# Shield_Release_181017.net
KiCad netlist of a schematic drawn in EAGLE
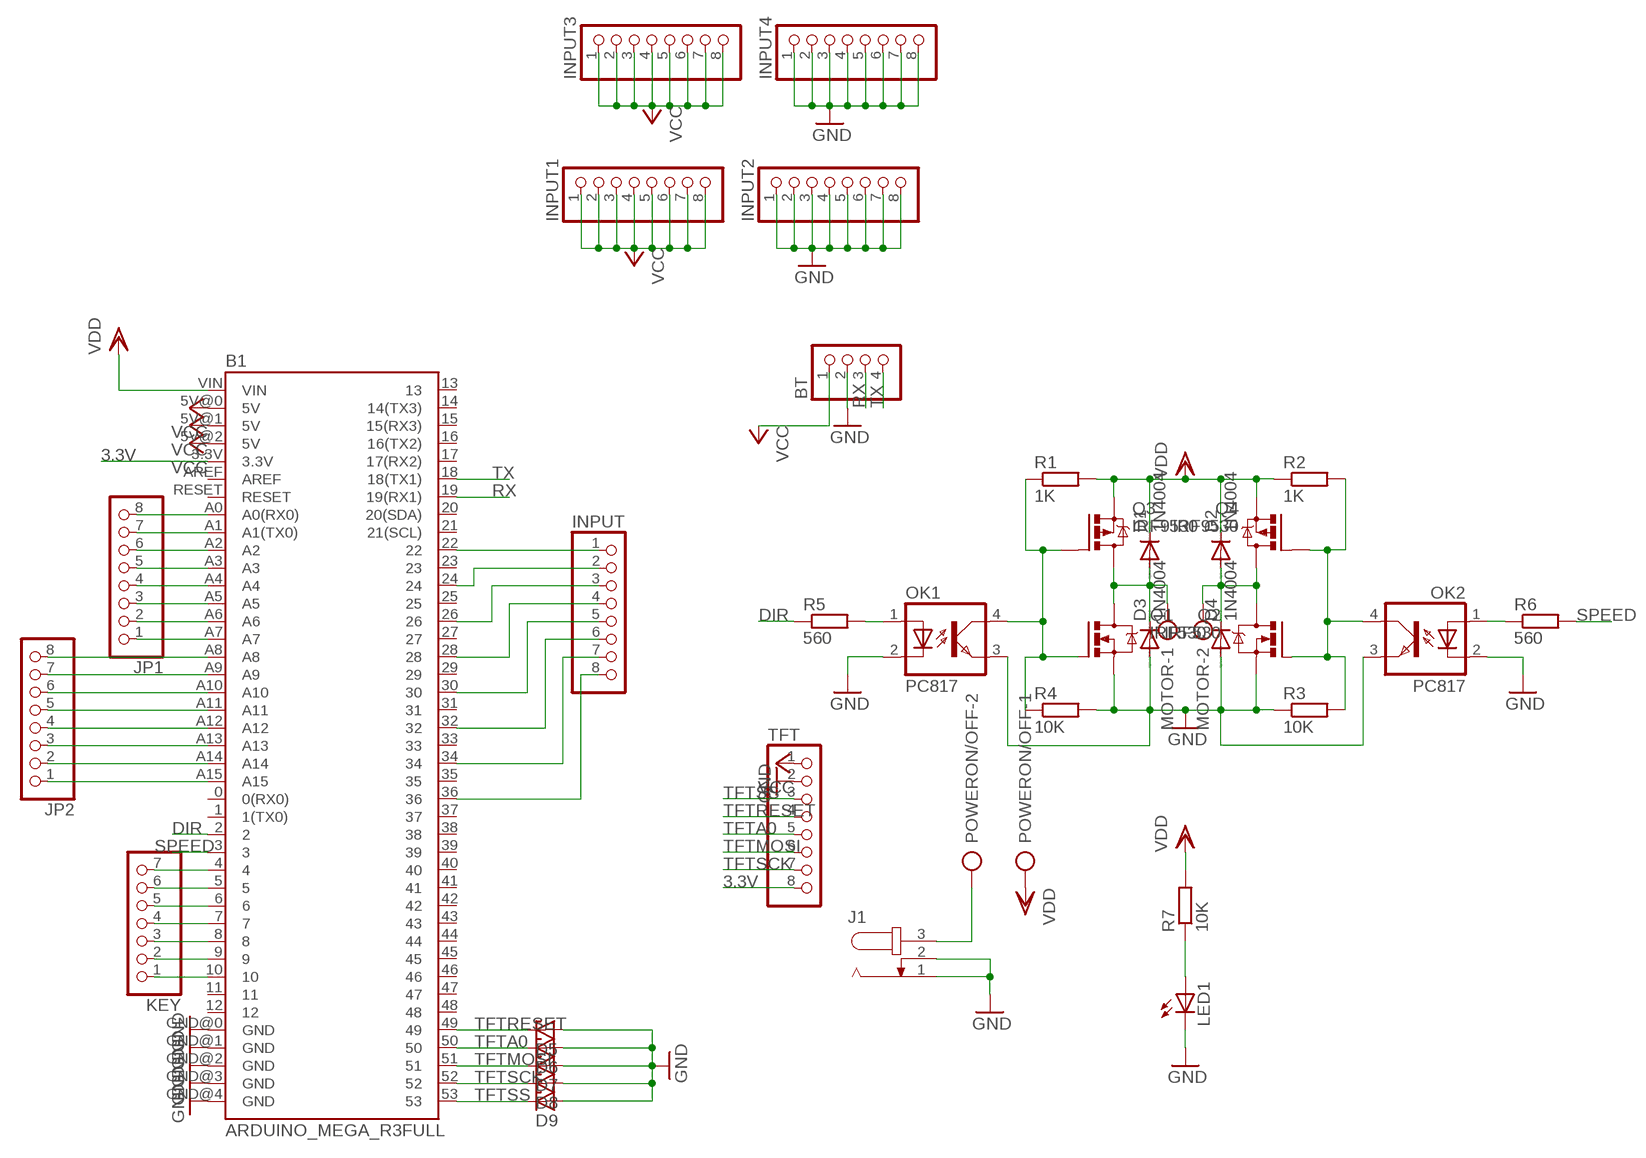
[diagram p0: schematic, sheet 1]

(export (version "E")
  (design (tool "Eeschema 10.0.6"))
  (components
    (comp (ref "B1")
      (value "ARDUINO_MEGA_R3FULL")
      (footprint "eagle-import:ARDUINO_MEGA")
      (libsource (lib "eagle-import") (part "ARDUINO_MEGA_R3FULL"))
    )
    (comp (ref "BT")
      (value "PINHD-1X4")
      (footprint "eagle-import:1X04")
      (libsource (lib "eagle-import") (part "PINHD-1X4"))
    )
    (comp (ref "D1")
      (value "1N4004")
      (footprint "eagle-import:DO41-10")
      (libsource (lib "eagle-import") (part "1N4004"))
    )
    (comp (ref "D2")
      (value "1N4004")
      (footprint "eagle-import:DO41-10")
      (libsource (lib "eagle-import") (part "1N4004"))
    )
    (comp (ref "D3")
      (value "1N4004")
      (footprint "eagle-import:DO41-10")
      (libsource (lib "eagle-import") (part "1N4004"))
    )
    (comp (ref "D4")
      (value "1N4004")
      (footprint "eagle-import:DO41-10")
      (libsource (lib "eagle-import") (part "1N4004"))
    )
    (comp (ref "D5")
      (value "ZENER-DIODEDO41Z10")
      (footprint "eagle-import:DO41Z10")
      (libsource (lib "eagle-import") (part "ZENER-DIODEDO41Z10"))
    )
    (comp (ref "D6")
      (value "ZENER-DIODEDO41Z10")
      (footprint "eagle-import:DO41Z10")
      (libsource (lib "eagle-import") (part "ZENER-DIODEDO41Z10"))
    )
    (comp (ref "D7")
      (value "ZENER-DIODEDO41Z10")
      (footprint "eagle-import:DO41Z10")
      (libsource (lib "eagle-import") (part "ZENER-DIODEDO41Z10"))
    )
    (comp (ref "D8")
      (value "ZENER-DIODEDO41Z10")
      (footprint "eagle-import:DO41Z10")
      (libsource (lib "eagle-import") (part "ZENER-DIODEDO41Z10"))
    )
    (comp (ref "D9")
      (value "ZENER-DIODEDO41Z10")
      (footprint "eagle-import:DO41Z10")
      (libsource (lib "eagle-import") (part "ZENER-DIODEDO41Z10"))
    )
    (comp (ref "INPUT")
      (value "PINHD-1X8")
      (footprint "eagle-import:1X08")
      (libsource (lib "eagle-import") (part "PINHD-1X8"))
    )
    (comp (ref "INPUT1")
      (value "PINHD-1X8")
      (footprint "eagle-import:1X08")
      (libsource (lib "eagle-import") (part "PINHD-1X8"))
    )
    (comp (ref "INPUT2")
      (value "PINHD-1X8")
      (footprint "eagle-import:1X08")
      (libsource (lib "eagle-import") (part "PINHD-1X8"))
    )
    (comp (ref "INPUT3")
      (value "PINHD-1X8")
      (footprint "eagle-import:1X08")
      (libsource (lib "eagle-import") (part "PINHD-1X8"))
    )
    (comp (ref "INPUT4")
      (value "PINHD-1X8")
      (footprint "eagle-import:1X08")
      (libsource (lib "eagle-import") (part "PINHD-1X8"))
    )
    (comp (ref "J1")
      (value "JACK-PLUG0")
      (footprint "eagle-import:SPC4077")
      (libsource (lib "eagle-import") (part "JACK-PLUG0"))
    )
    (comp (ref "JP1")
      (value "PINHD-1X8")
      (footprint "eagle-import:1X08")
      (libsource (lib "eagle-import") (part "PINHD-1X8"))
    )
    (comp (ref "JP2")
      (value "PINHD-1X8")
      (footprint "eagle-import:1X08")
      (libsource (lib "eagle-import") (part "PINHD-1X8"))
    )
    (comp (ref "KEY")
      (value "PINHD-1X7")
      (footprint "eagle-import:1X07")
      (libsource (lib "eagle-import") (part "PINHD-1X7"))
    )
    (comp (ref "LED1")
      (value "LED5MM")
      (footprint "eagle-import:LED5MM")
      (libsource (lib "eagle-import") (part "LED5MM"))
    )
    (comp (ref "MOTOR")
      (value "AK300/2")
      (footprint "eagle-import:AK300_2")
      (libsource (lib "eagle-import") (part "AK300/2"))
    )
    (comp (ref "OK1")
      (value "PC817")
      (footprint "eagle-import:DIL04")
      (fields (field (name "MPN") "PC817X4J000F"))
      (libsource (lib "eagle-import") (part "PC817"))
    )
    (comp (ref "OK2")
      (value "PC817")
      (footprint "eagle-import:DIL04")
      (fields (field (name "MPN") "PC817X4J000F"))
      (libsource (lib "eagle-import") (part "PC817"))
    )
    (comp (ref "POWERON/OFF")
      (value "AK300/2")
      (footprint "eagle-import:AK300_2")
      (libsource (lib "eagle-import") (part "AK300/2"))
    )
    (comp (ref "Q1")
      (value "IRF530")
      (footprint "eagle-import:TO220BV")
      (libsource (lib "eagle-import") (part "IRF530"))
    )
    (comp (ref "Q2")
      (value "IRF530")
      (footprint "eagle-import:TO220BV")
      (libsource (lib "eagle-import") (part "IRF530"))
    )
    (comp (ref "Q3")
      (value "IRF9530")
      (footprint "eagle-import:TO220BV")
      (libsource (lib "eagle-import") (part "IRF9530"))
    )
    (comp (ref "Q4")
      (value "IRF9530")
      (footprint "eagle-import:TO220BV")
      (libsource (lib "eagle-import") (part "IRF9530"))
    )
    (comp (ref "R1")
      (value "1K")
      (footprint "eagle-import:0204_7")
      (libsource (lib "eagle-import") (part "R-EU_0204/7"))
    )
    (comp (ref "R2")
      (value "1K")
      (footprint "eagle-import:0204_7")
      (libsource (lib "eagle-import") (part "R-EU_0204/7"))
    )
    (comp (ref "R3")
      (value "10K")
      (footprint "eagle-import:0204_7")
      (libsource (lib "eagle-import") (part "R-EU_0204/7"))
    )
    (comp (ref "R4")
      (value "10K")
      (footprint "eagle-import:0204_7")
      (libsource (lib "eagle-import") (part "R-EU_0204/7"))
    )
    (comp (ref "R5")
      (value "560")
      (footprint "eagle-import:0204_7")
      (libsource (lib "eagle-import") (part "R-EU_0204/7"))
    )
    (comp (ref "R6")
      (value "560")
      (footprint "eagle-import:0204_7")
      (libsource (lib "eagle-import") (part "R-EU_0204/7"))
    )
    (comp (ref "R7")
      (value "10K")
      (footprint "eagle-import:0204_7")
      (libsource (lib "eagle-import") (part "R-EU_0204/7"))
    )
    (comp (ref "TFT")
      (value "PINHD-1X8")
      (footprint "eagle-import:1X08")
      (libsource (lib "eagle-import") (part "PINHD-1X8"))
    )
  )
  (nets
    (net (code "1") (name "/3.3V") (class "Default")
      (node (ref "B1") (pin "3.3V") (pinfunction "3.3V_3.3V") (pintype "bidirectional"))
      (node (ref "TFT") (pin "8") (pinfunction "8_8") (pintype "passive"))
    )
    (net (code "2") (name "/DIR") (class "Default")
      (node (ref "B1") (pin "2") (pinfunction "2_2") (pintype "bidirectional"))
      (node (ref "R5") (pin "1") (pinfunction "1_1") (pintype "passive"))
    )
    (net (code "3") (name "/RX") (class "Default")
      (node (ref "B1") (pin "19") (pinfunction "19(RX1)_19") (pintype "bidirectional"))
      (node (ref "BT") (pin "3") (pinfunction "3_3") (pintype "passive"))
    )
    (net (code "4") (name "/SPEED") (class "Default")
      (node (ref "B1") (pin "3") (pinfunction "3_3") (pintype "bidirectional"))
      (node (ref "R6") (pin "2") (pinfunction "2_2") (pintype "passive"))
    )
    (net (code "5") (name "/TFTA0") (class "Default")
      (node (ref "B1") (pin "50") (pinfunction "50_50") (pintype "bidirectional"))
      (node (ref "D6") (pin "C") (pinfunction "C_C") (pintype "passive"))
      (node (ref "TFT") (pin "5") (pinfunction "5_5") (pintype "passive"))
    )
    (net (code "6") (name "/TFTMOSI") (class "Default")
      (node (ref "B1") (pin "51") (pinfunction "51_51") (pintype "bidirectional"))
      (node (ref "D7") (pin "C") (pinfunction "C_C") (pintype "passive"))
      (node (ref "TFT") (pin "6") (pinfunction "6_6") (pintype "passive"))
    )
    (net (code "7") (name "/TFTRESET") (class "Default")
      (node (ref "B1") (pin "49") (pinfunction "49_49") (pintype "bidirectional"))
      (node (ref "D5") (pin "C") (pinfunction "C_C") (pintype "passive"))
      (node (ref "TFT") (pin "4") (pinfunction "4_4") (pintype "passive"))
    )
    (net (code "8") (name "/TFTSCK") (class "Default")
      (node (ref "B1") (pin "52") (pinfunction "52_52") (pintype "bidirectional"))
      (node (ref "D8") (pin "C") (pinfunction "C_C") (pintype "passive"))
      (node (ref "TFT") (pin "7") (pinfunction "7_7") (pintype "passive"))
    )
    (net (code "9") (name "/TFTSS") (class "Default")
      (node (ref "B1") (pin "53") (pinfunction "53_53") (pintype "bidirectional"))
      (node (ref "D9") (pin "C") (pinfunction "C_C") (pintype "passive"))
      (node (ref "TFT") (pin "3") (pinfunction "3_3") (pintype "passive"))
    )
    (net (code "10") (name "/TX") (class "Default")
      (node (ref "B1") (pin "18") (pinfunction "18(TX1)_18") (pintype "bidirectional"))
      (node (ref "BT") (pin "4") (pinfunction "4_4") (pintype "passive"))
    )
    (net (code "11") (name "GND") (class "Default")
      (node (ref "B1") (pin "GND@0") (pinfunction "GND_GND@0") (pintype "bidirectional"))
      (node (ref "B1") (pin "GND@1") (pinfunction "GND_GND@1") (pintype "bidirectional"))
      (node (ref "B1") (pin "GND@2") (pinfunction "GND_GND@2") (pintype "bidirectional"))
      (node (ref "B1") (pin "GND@3") (pinfunction "GND_GND@3") (pintype "bidirectional"))
      (node (ref "B1") (pin "GND@4") (pinfunction "GND_GND@4") (pintype "bidirectional"))
      (node (ref "BT") (pin "2") (pinfunction "2_2") (pintype "passive"))
      (node (ref "D3") (pin "A") (pinfunction "A_A") (pintype "passive"))
      (node (ref "D4") (pin "A") (pinfunction "A_A") (pintype "passive"))
      (node (ref "D5") (pin "A") (pinfunction "A_A") (pintype "passive"))
      (node (ref "D6") (pin "A") (pinfunction "A_A") (pintype "passive"))
      (node (ref "D7") (pin "A") (pinfunction "A_A") (pintype "passive"))
      (node (ref "D8") (pin "A") (pinfunction "A_A") (pintype "passive"))
      (node (ref "D9") (pin "A") (pinfunction "A_A") (pintype "passive"))
      (node (ref "INPUT2") (pin "1") (pinfunction "1_1") (pintype "passive"))
      (node (ref "INPUT2") (pin "2") (pinfunction "2_2") (pintype "passive"))
      (node (ref "INPUT2") (pin "3") (pinfunction "3_3") (pintype "passive"))
      (node (ref "INPUT2") (pin "4") (pinfunction "4_4") (pintype "passive"))
      (node (ref "INPUT2") (pin "5") (pinfunction "5_5") (pintype "passive"))
      (node (ref "INPUT2") (pin "6") (pinfunction "6_6") (pintype "passive"))
      (node (ref "INPUT2") (pin "7") (pinfunction "7_7") (pintype "passive"))
      (node (ref "INPUT2") (pin "8") (pinfunction "8_8") (pintype "passive"))
      (node (ref "INPUT4") (pin "1") (pinfunction "1_1") (pintype "passive"))
      (node (ref "INPUT4") (pin "2") (pinfunction "2_2") (pintype "passive"))
      (node (ref "INPUT4") (pin "3") (pinfunction "3_3") (pintype "passive"))
      (node (ref "INPUT4") (pin "4") (pinfunction "4_4") (pintype "passive"))
      (node (ref "INPUT4") (pin "5") (pinfunction "5_5") (pintype "passive"))
      (node (ref "INPUT4") (pin "6") (pinfunction "6_6") (pintype "passive"))
      (node (ref "INPUT4") (pin "7") (pinfunction "7_7") (pintype "passive"))
      (node (ref "INPUT4") (pin "8") (pinfunction "8_8") (pintype "passive"))
      (node (ref "J1") (pin "1") (pinfunction "1_1") (pintype "passive"))
      (node (ref "J1") (pin "2") (pinfunction "2_2") (pintype "passive"))
      (node (ref "LED1") (pin "K") (pinfunction "C_K") (pintype "passive"))
      (node (ref "OK1") (pin "2") (pinfunction "C_2") (pintype "passive"))
      (node (ref "OK1") (pin "3") (pinfunction "EMIT_3") (pintype "passive"))
      (node (ref "OK2") (pin "2") (pinfunction "C_2") (pintype "passive"))
      (node (ref "OK2") (pin "3") (pinfunction "EMIT_3") (pintype "passive"))
      (node (ref "Q1") (pin "S") (pinfunction "S_S") (pintype "passive"))
      (node (ref "Q2") (pin "S") (pinfunction "S_S") (pintype "passive"))
      (node (ref "R3") (pin "1") (pinfunction "1_1") (pintype "passive"))
      (node (ref "R4") (pin "2") (pinfunction "2_2") (pintype "passive"))
      (node (ref "TFT") (pin "2") (pinfunction "2_2") (pintype "passive"))
    )
    (net (code "12") (name "Net-(B1-A0(RX0))") (class "Default")
      (node (ref "B1") (pin "A0") (pinfunction "A0(RX0)_A0") (pintype "bidirectional"))
      (node (ref "JP1") (pin "8") (pinfunction "8_8") (pintype "passive"))
    )
    (net (code "13") (name "Net-(B1-A1(TX0))") (class "Default")
      (node (ref "B1") (pin "A1") (pinfunction "A1(TX0)_A1") (pintype "bidirectional"))
      (node (ref "JP1") (pin "7") (pinfunction "7_7") (pintype "passive"))
    )
    (net (code "14") (name "Net-(B1-Pad4)") (class "Default")
      (node (ref "B1") (pin "4") (pinfunction "4_4") (pintype "bidirectional"))
      (node (ref "KEY") (pin "7") (pinfunction "7_7") (pintype "passive"))
    )
    (net (code "15") (name "Net-(B1-Pad5)") (class "Default")
      (node (ref "B1") (pin "5") (pinfunction "5_5") (pintype "bidirectional"))
      (node (ref "KEY") (pin "6") (pinfunction "6_6") (pintype "passive"))
    )
    (net (code "16") (name "Net-(B1-Pad6)") (class "Default")
      (node (ref "B1") (pin "6") (pinfunction "6_6") (pintype "bidirectional"))
      (node (ref "KEY") (pin "5") (pinfunction "5_5") (pintype "passive"))
    )
    (net (code "17") (name "Net-(B1-Pad7)") (class "Default")
      (node (ref "B1") (pin "7") (pinfunction "7_7") (pintype "bidirectional"))
      (node (ref "KEY") (pin "4") (pinfunction "4_4") (pintype "passive"))
    )
    (net (code "18") (name "Net-(B1-Pad8)") (class "Default")
      (node (ref "B1") (pin "8") (pinfunction "8_8") (pintype "bidirectional"))
      (node (ref "KEY") (pin "3") (pinfunction "3_3") (pintype "passive"))
    )
    (net (code "19") (name "Net-(B1-Pad9)") (class "Default")
      (node (ref "B1") (pin "9") (pinfunction "9_9") (pintype "bidirectional"))
      (node (ref "KEY") (pin "2") (pinfunction "2_2") (pintype "passive"))
    )
    (net (code "20") (name "Net-(B1-Pad10)") (class "Default")
      (node (ref "B1") (pin "10") (pinfunction "10_10") (pintype "bidirectional"))
      (node (ref "KEY") (pin "1") (pinfunction "1_1") (pintype "passive"))
    )
    (net (code "21") (name "Net-(B1-Pad22)") (class "Default")
      (node (ref "B1") (pin "22") (pinfunction "22_22") (pintype "bidirectional"))
      (node (ref "INPUT") (pin "1") (pinfunction "1_1") (pintype "passive"))
    )
    (net (code "22") (name "Net-(B1-Pad24)") (class "Default")
      (node (ref "B1") (pin "24") (pinfunction "24_24") (pintype "bidirectional"))
      (node (ref "INPUT") (pin "2") (pinfunction "2_2") (pintype "passive"))
    )
    (net (code "23") (name "Net-(B1-Pad26)") (class "Default")
      (node (ref "B1") (pin "26") (pinfunction "26_26") (pintype "bidirectional"))
      (node (ref "INPUT") (pin "3") (pinfunction "3_3") (pintype "passive"))
    )
    (net (code "24") (name "Net-(B1-Pad28)") (class "Default")
      (node (ref "B1") (pin "28") (pinfunction "28_28") (pintype "bidirectional"))
      (node (ref "INPUT") (pin "4") (pinfunction "4_4") (pintype "passive"))
    )
    (net (code "25") (name "Net-(B1-Pad30)") (class "Default")
      (node (ref "B1") (pin "30") (pinfunction "30_30") (pintype "bidirectional"))
      (node (ref "INPUT") (pin "5") (pinfunction "5_5") (pintype "passive"))
    )
    (net (code "26") (name "Net-(B1-Pad32)") (class "Default")
      (node (ref "B1") (pin "32") (pinfunction "32_32") (pintype "bidirectional"))
      (node (ref "INPUT") (pin "6") (pinfunction "6_6") (pintype "passive"))
    )
    (net (code "27") (name "Net-(B1-Pad34)") (class "Default")
      (node (ref "B1") (pin "34") (pinfunction "34_34") (pintype "bidirectional"))
      (node (ref "INPUT") (pin "7") (pinfunction "7_7") (pintype "passive"))
    )
    (net (code "28") (name "Net-(B1-Pad36)") (class "Default")
      (node (ref "B1") (pin "36") (pinfunction "36_36") (pintype "bidirectional"))
      (node (ref "INPUT") (pin "8") (pinfunction "8_8") (pintype "passive"))
    )
    (net (code "29") (name "Net-(B1-PadA2)") (class "Default")
      (node (ref "B1") (pin "A2") (pinfunction "A2_A2") (pintype "bidirectional"))
      (node (ref "JP1") (pin "6") (pinfunction "6_6") (pintype "passive"))
    )
    (net (code "30") (name "Net-(B1-PadA3)") (class "Default")
      (node (ref "B1") (pin "A3") (pinfunction "A3_A3") (pintype "bidirectional"))
      (node (ref "JP1") (pin "5") (pinfunction "5_5") (pintype "passive"))
    )
    (net (code "31") (name "Net-(B1-PadA4)") (class "Default")
      (node (ref "B1") (pin "A4") (pinfunction "A4_A4") (pintype "bidirectional"))
      (node (ref "JP1") (pin "4") (pinfunction "4_4") (pintype "passive"))
    )
    (net (code "32") (name "Net-(B1-PadA5)") (class "Default")
      (node (ref "B1") (pin "A5") (pinfunction "A5_A5") (pintype "bidirectional"))
      (node (ref "JP1") (pin "3") (pinfunction "3_3") (pintype "passive"))
    )
    (net (code "33") (name "Net-(B1-PadA6)") (class "Default")
      (node (ref "B1") (pin "A6") (pinfunction "A6_A6") (pintype "bidirectional"))
      (node (ref "JP1") (pin "2") (pinfunction "2_2") (pintype "passive"))
    )
    (net (code "34") (name "Net-(B1-PadA7)") (class "Default")
      (node (ref "B1") (pin "A7") (pinfunction "A7_A7") (pintype "bidirectional"))
      (node (ref "JP1") (pin "1") (pinfunction "1_1") (pintype "passive"))
    )
    (net (code "35") (name "Net-(B1-PadA8)") (class "Default")
      (node (ref "B1") (pin "A8") (pinfunction "A8_A8") (pintype "bidirectional"))
      (node (ref "JP2") (pin "8") (pinfunction "8_8") (pintype "passive"))
    )
    (net (code "36") (name "Net-(B1-PadA9)") (class "Default")
      (node (ref "B1") (pin "A9") (pinfunction "A9_A9") (pintype "bidirectional"))
      (node (ref "JP2") (pin "7") (pinfunction "7_7") (pintype "passive"))
    )
    (net (code "37") (name "Net-(B1-PadA10)") (class "Default")
      (node (ref "B1") (pin "A10") (pinfunction "A10_A10") (pintype "bidirectional"))
      (node (ref "JP2") (pin "6") (pinfunction "6_6") (pintype "passive"))
    )
    (net (code "38") (name "Net-(B1-PadA11)") (class "Default")
      (node (ref "B1") (pin "A11") (pinfunction "A11_A11") (pintype "bidirectional"))
      (node (ref "JP2") (pin "5") (pinfunction "5_5") (pintype "passive"))
    )
    (net (code "39") (name "Net-(B1-PadA12)") (class "Default")
      (node (ref "B1") (pin "A12") (pinfunction "A12_A12") (pintype "bidirectional"))
      (node (ref "JP2") (pin "4") (pinfunction "4_4") (pintype "passive"))
    )
    (net (code "40") (name "Net-(B1-PadA13)") (class "Default")
      (node (ref "B1") (pin "A13") (pinfunction "A13_A13") (pintype "bidirectional"))
      (node (ref "JP2") (pin "3") (pinfunction "3_3") (pintype "passive"))
    )
    (net (code "41") (name "Net-(B1-PadA14)") (class "Default")
      (node (ref "B1") (pin "A14") (pinfunction "A14_A14") (pintype "bidirectional"))
      (node (ref "JP2") (pin "2") (pinfunction "2_2") (pintype "passive"))
    )
    (net (code "42") (name "Net-(B1-PadA15)") (class "Default")
      (node (ref "B1") (pin "A15") (pinfunction "A15_A15") (pintype "bidirectional"))
      (node (ref "JP2") (pin "1") (pinfunction "1_1") (pintype "passive"))
    )
    (net (code "43") (name "Net-(LED1-PadA)") (class "Default")
      (node (ref "LED1") (pin "A") (pinfunction "A_A") (pintype "passive"))
      (node (ref "R7") (pin "1") (pinfunction "1_1") (pintype "passive"))
    )
    (net (code "44") (name "Net-(MOTORA-KL)") (class "Default")
      (node (ref "D1") (pin "A") (pinfunction "A_A") (pintype "passive"))
      (node (ref "D3") (pin "C") (pinfunction "C_C") (pintype "passive"))
      (node (ref "MOTOR") (pin "1") (pinfunction "KL_1") (pintype "passive"))
      (node (ref "Q1") (pin "D") (pinfunction "D_D") (pintype "passive"))
      (node (ref "Q3") (pin "D") (pinfunction "D_D") (pintype "passive"))
    )
    (net (code "45") (name "Net-(MOTORB-KL)") (class "Default")
      (node (ref "D2") (pin "A") (pinfunction "A_A") (pintype "passive"))
      (node (ref "D4") (pin "C") (pinfunction "C_C") (pintype "passive"))
      (node (ref "MOTOR") (pin "2") (pinfunction "KL_2") (pintype "passive"))
      (node (ref "Q2") (pin "D") (pinfunction "D_D") (pintype "passive"))
      (node (ref "Q4") (pin "D") (pinfunction "D_D") (pintype "passive"))
    )
    (net (code "46") (name "Net-(OK1-A)") (class "Default")
      (node (ref "OK1") (pin "1") (pinfunction "A_1") (pintype "passive"))
      (node (ref "R5") (pin "2") (pinfunction "2_2") (pintype "passive"))
    )
    (net (code "47") (name "Net-(OK1-COL)") (class "Default")
      (node (ref "OK1") (pin "4") (pinfunction "COL_4") (pintype "passive"))
      (node (ref "Q1") (pin "G") (pinfunction "G_G") (pintype "passive"))
      (node (ref "Q3") (pin "G") (pinfunction "G_G") (pintype "passive"))
      (node (ref "R1") (pin "1") (pinfunction "1_1") (pintype "passive"))
      (node (ref "R4") (pin "1") (pinfunction "1_1") (pintype "passive"))
    )
    (net (code "48") (name "Net-(OK2-A)") (class "Default")
      (node (ref "OK2") (pin "1") (pinfunction "A_1") (pintype "passive"))
      (node (ref "R6") (pin "1") (pinfunction "1_1") (pintype "passive"))
    )
    (net (code "49") (name "Net-(OK2-COL)") (class "Default")
      (node (ref "OK2") (pin "4") (pinfunction "COL_4") (pintype "passive"))
      (node (ref "Q2") (pin "G") (pinfunction "G_G") (pintype "passive"))
      (node (ref "Q4") (pin "G") (pinfunction "G_G") (pintype "passive"))
      (node (ref "R2") (pin "2") (pinfunction "2_2") (pintype "passive"))
      (node (ref "R3") (pin "2") (pinfunction "2_2") (pintype "passive"))
    )
    (net (code "50") (name "Net-(POWERON/OFFB-KL)") (class "Default")
      (node (ref "J1") (pin "3") (pinfunction "3_3") (pintype "passive"))
      (node (ref "POWERON/OFF") (pin "2") (pinfunction "KL_2") (pintype "passive"))
    )
    (net (code "51") (name "VCC") (class "Default")
      (node (ref "B1") (pin "5V@0") (pinfunction "5V_5V@0") (pintype "bidirectional"))
      (node (ref "B1") (pin "5V@1") (pinfunction "5V_5V@1") (pintype "bidirectional"))
      (node (ref "B1") (pin "5V@2") (pinfunction "5V_5V@2") (pintype "bidirectional"))
      (node (ref "BT") (pin "1") (pinfunction "1_1") (pintype "passive"))
      (node (ref "INPUT1") (pin "1") (pinfunction "1_1") (pintype "passive"))
      (node (ref "INPUT1") (pin "2") (pinfunction "2_2") (pintype "passive"))
      (node (ref "INPUT1") (pin "3") (pinfunction "3_3") (pintype "passive"))
      (node (ref "INPUT1") (pin "4") (pinfunction "4_4") (pintype "passive"))
      (node (ref "INPUT1") (pin "5") (pinfunction "5_5") (pintype "passive"))
      (node (ref "INPUT1") (pin "6") (pinfunction "6_6") (pintype "passive"))
      (node (ref "INPUT1") (pin "7") (pinfunction "7_7") (pintype "passive"))
      (node (ref "INPUT1") (pin "8") (pinfunction "8_8") (pintype "passive"))
      (node (ref "INPUT3") (pin "1") (pinfunction "1_1") (pintype "passive"))
      (node (ref "INPUT3") (pin "2") (pinfunction "2_2") (pintype "passive"))
      (node (ref "INPUT3") (pin "3") (pinfunction "3_3") (pintype "passive"))
      (node (ref "INPUT3") (pin "4") (pinfunction "4_4") (pintype "passive"))
      (node (ref "INPUT3") (pin "5") (pinfunction "5_5") (pintype "passive"))
      (node (ref "INPUT3") (pin "6") (pinfunction "6_6") (pintype "passive"))
      (node (ref "INPUT3") (pin "7") (pinfunction "7_7") (pintype "passive"))
      (node (ref "INPUT3") (pin "8") (pinfunction "8_8") (pintype "passive"))
      (node (ref "TFT") (pin "1") (pinfunction "1_1") (pintype "passive"))
    )
    (net (code "52") (name "VDD") (class "Default")
      (node (ref "B1") (pin "VIN") (pinfunction "VIN_VIN") (pintype "bidirectional"))
      (node (ref "D1") (pin "C") (pinfunction "C_C") (pintype "passive"))
      (node (ref "D2") (pin "C") (pinfunction "C_C") (pintype "passive"))
      (node (ref "POWERON/OFF") (pin "1") (pinfunction "KL_1") (pintype "passive"))
      (node (ref "Q3") (pin "S") (pinfunction "S_S") (pintype "passive"))
      (node (ref "Q4") (pin "S") (pinfunction "S_S") (pintype "passive"))
      (node (ref "R1") (pin "2") (pinfunction "2_2") (pintype "passive"))
      (node (ref "R2") (pin "1") (pinfunction "1_1") (pintype "passive"))
      (node (ref "R7") (pin "2") (pinfunction "2_2") (pintype "passive"))
    )
    (net (code "53") (name "unconnected-(B1-0(RX0)-Pad0)") (class "Default")
      (node (ref "B1") (pin "0") (pinfunction "0(RX0)_0") (pintype "bidirectional"))
    )
    (net (code "54") (name "unconnected-(B1-1(TX0)-Pad1)") (class "Default")
      (node (ref "B1") (pin "1") (pinfunction "1(TX0)_1") (pintype "bidirectional"))
    )
    (net (code "55") (name "unconnected-(B1-14(TX3)-Pad14)") (class "Default")
      (node (ref "B1") (pin "14") (pinfunction "14(TX3)_14") (pintype "bidirectional"))
    )
    (net (code "56") (name "unconnected-(B1-15(RX3)-Pad15)") (class "Default")
      (node (ref "B1") (pin "15") (pinfunction "15(RX3)_15") (pintype "bidirectional"))
    )
    (net (code "57") (name "unconnected-(B1-16(TX2)-Pad16)") (class "Default")
      (node (ref "B1") (pin "16") (pinfunction "16(TX2)_16") (pintype "bidirectional"))
    )
    (net (code "58") (name "unconnected-(B1-17(RX2)-Pad17)") (class "Default")
      (node (ref "B1") (pin "17") (pinfunction "17(RX2)_17") (pintype "bidirectional"))
    )
    (net (code "59") (name "unconnected-(B1-20(SDA)-Pad20)") (class "Default")
      (node (ref "B1") (pin "20") (pinfunction "20(SDA)_20") (pintype "bidirectional"))
    )
    (net (code "60") (name "unconnected-(B1-21(SCL)-Pad21)") (class "Default")
      (node (ref "B1") (pin "21") (pinfunction "21(SCL)_21") (pintype "bidirectional"))
    )
    (net (code "61") (name "unconnected-(B1-Pad11)") (class "Default")
      (node (ref "B1") (pin "11") (pinfunction "11_11") (pintype "bidirectional"))
    )
    (net (code "62") (name "unconnected-(B1-Pad12)") (class "Default")
      (node (ref "B1") (pin "12") (pinfunction "12_12") (pintype "bidirectional"))
    )
    (net (code "63") (name "unconnected-(B1-Pad13)") (class "Default")
      (node (ref "B1") (pin "13") (pinfunction "13_13") (pintype "bidirectional"))
    )
    (net (code "64") (name "unconnected-(B1-Pad23)") (class "Default")
      (node (ref "B1") (pin "23") (pinfunction "23_23") (pintype "bidirectional"))
    )
    (net (code "65") (name "unconnected-(B1-Pad25)") (class "Default")
      (node (ref "B1") (pin "25") (pinfunction "25_25") (pintype "bidirectional"))
    )
    (net (code "66") (name "unconnected-(B1-Pad27)") (class "Default")
      (node (ref "B1") (pin "27") (pinfunction "27_27") (pintype "bidirectional"))
    )
    (net (code "67") (name "unconnected-(B1-Pad29)") (class "Default")
      (node (ref "B1") (pin "29") (pinfunction "29_29") (pintype "bidirectional"))
    )
    (net (code "68") (name "unconnected-(B1-Pad31)") (class "Default")
      (node (ref "B1") (pin "31") (pinfunction "31_31") (pintype "bidirectional"))
    )
    (net (code "69") (name "unconnected-(B1-Pad33)") (class "Default")
      (node (ref "B1") (pin "33") (pinfunction "33_33") (pintype "bidirectional"))
    )
    (net (code "70") (name "unconnected-(B1-Pad35)") (class "Default")
      (node (ref "B1") (pin "35") (pinfunction "35_35") (pintype "bidirectional"))
    )
    (net (code "71") (name "unconnected-(B1-Pad37)") (class "Default")
      (node (ref "B1") (pin "37") (pinfunction "37_37") (pintype "bidirectional"))
    )
    (net (code "72") (name "unconnected-(B1-Pad38)") (class "Default")
      (node (ref "B1") (pin "38") (pinfunction "38_38") (pintype "bidirectional"))
    )
    (net (code "73") (name "unconnected-(B1-Pad39)") (class "Default")
      (node (ref "B1") (pin "39") (pinfunction "39_39") (pintype "bidirectional"))
    )
    (net (code "74") (name "unconnected-(B1-Pad40)") (class "Default")
      (node (ref "B1") (pin "40") (pinfunction "40_40") (pintype "bidirectional"))
    )
    (net (code "75") (name "unconnected-(B1-Pad41)") (class "Default")
      (node (ref "B1") (pin "41") (pinfunction "41_41") (pintype "bidirectional"))
    )
    (net (code "76") (name "unconnected-(B1-Pad42)") (class "Default")
      (node (ref "B1") (pin "42") (pinfunction "42_42") (pintype "bidirectional"))
    )
    (net (code "77") (name "unconnected-(B1-Pad43)") (class "Default")
      (node (ref "B1") (pin "43") (pinfunction "43_43") (pintype "bidirectional"))
    )
    (net (code "78") (name "unconnected-(B1-Pad44)") (class "Default")
      (node (ref "B1") (pin "44") (pinfunction "44_44") (pintype "bidirectional"))
    )
    (net (code "79") (name "unconnected-(B1-Pad45)") (class "Default")
      (node (ref "B1") (pin "45") (pinfunction "45_45") (pintype "bidirectional"))
    )
    (net (code "80") (name "unconnected-(B1-Pad46)") (class "Default")
      (node (ref "B1") (pin "46") (pinfunction "46_46") (pintype "bidirectional"))
    )
    (net (code "81") (name "unconnected-(B1-Pad47)") (class "Default")
      (node (ref "B1") (pin "47") (pinfunction "47_47") (pintype "bidirectional"))
    )
    (net (code "82") (name "unconnected-(B1-Pad48)") (class "Default")
      (node (ref "B1") (pin "48") (pinfunction "48_48") (pintype "bidirectional"))
    )
    (net (code "83") (name "unconnected-(B1-PadAREF)") (class "Default")
      (node (ref "B1") (pin "AREF") (pinfunction "AREF_AREF") (pintype "bidirectional"))
    )
    (net (code "84") (name "unconnected-(B1-PadRESET)") (class "Default")
      (node (ref "B1") (pin "RESET") (pinfunction "RESET_RESET") (pintype "bidirectional"))
    )
  )
)
